# driver1.net
KiCad netlist of a schematic drawn in EAGLE
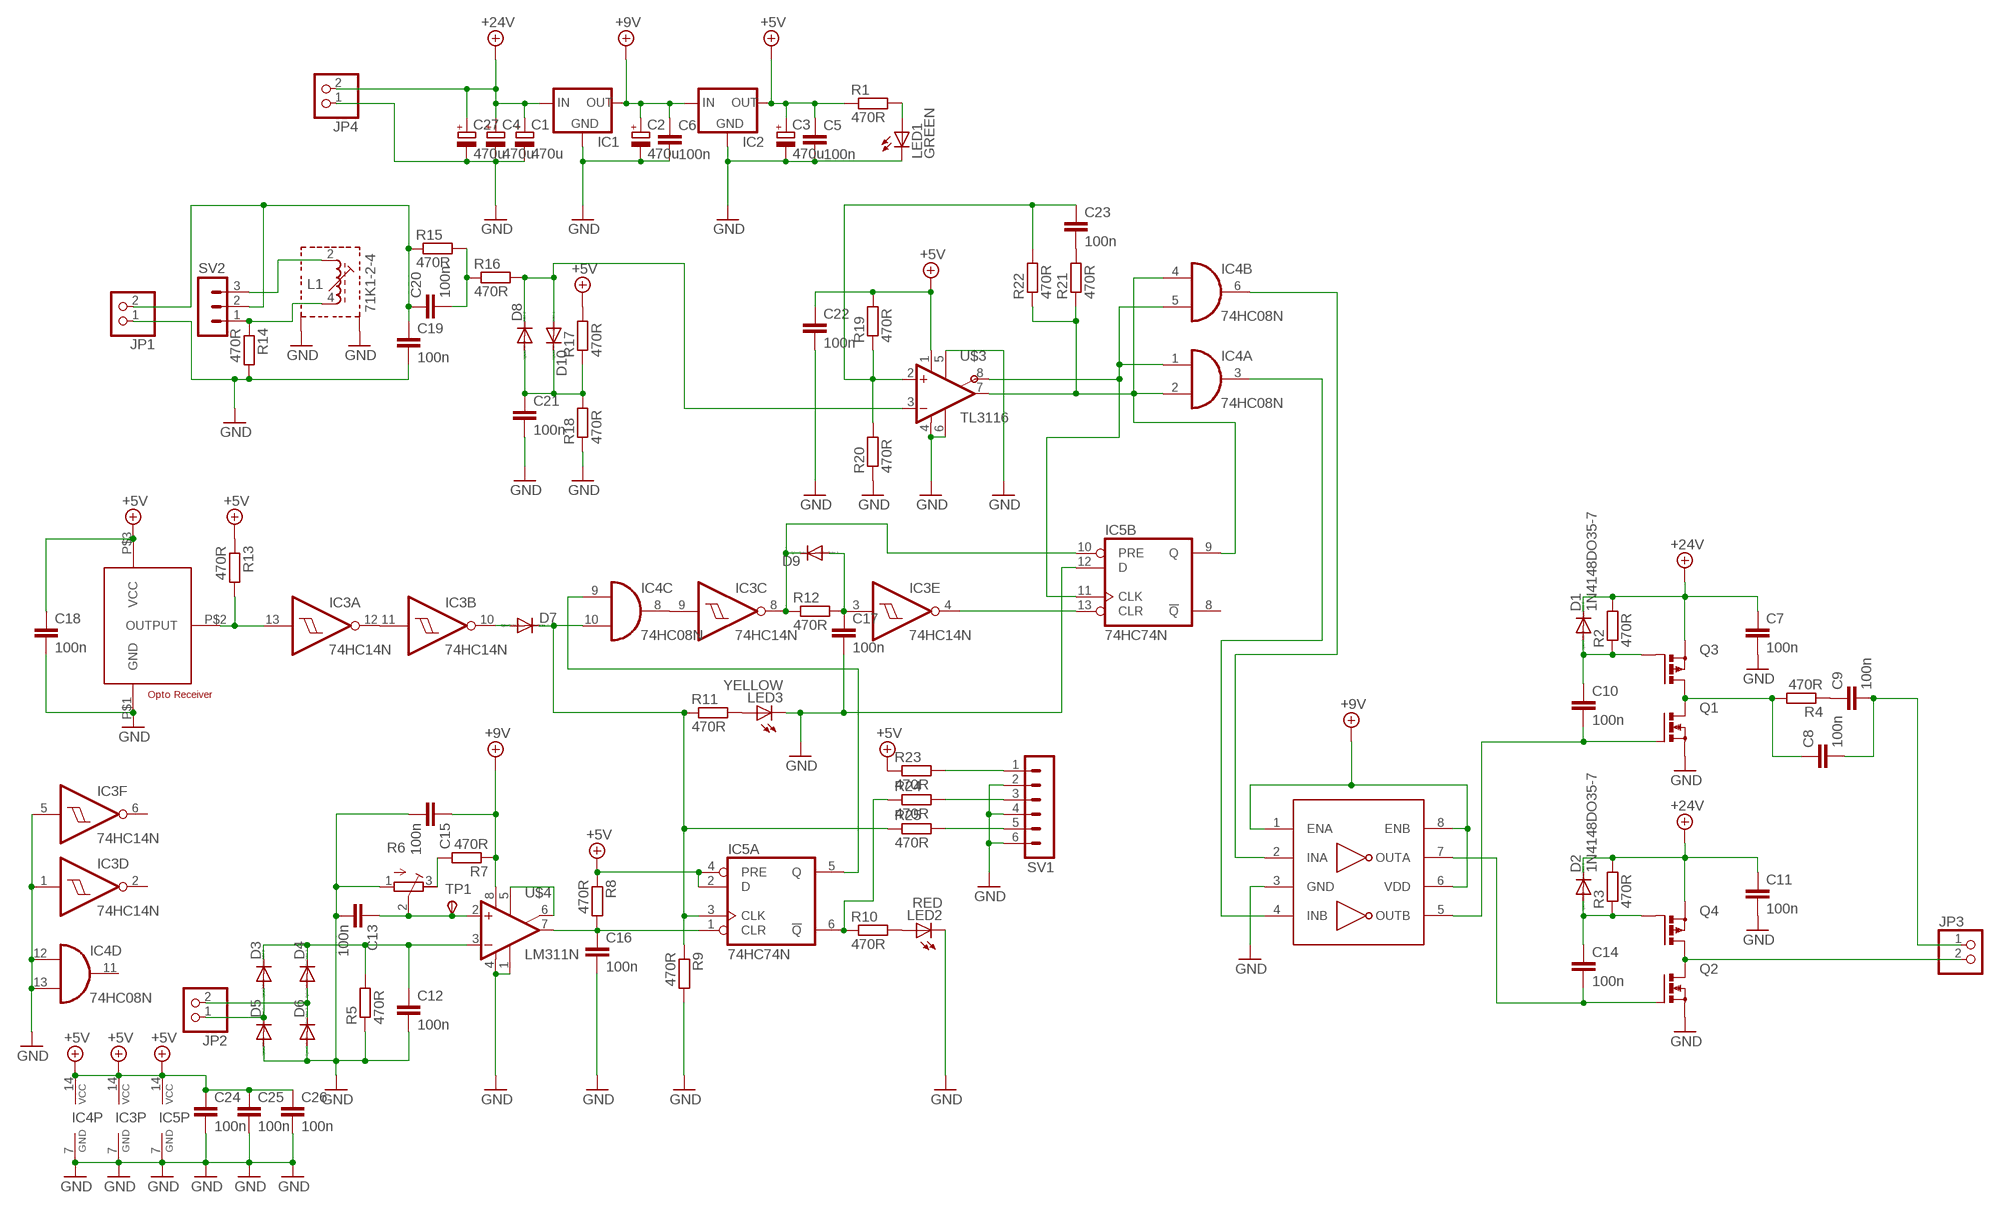
[diagram p0: schematic, sheet 1]

(export (version "E")
  (design (tool "Eeschema 10.0.6"))
  (components
    (comp (ref "C1")
      (value "470u")
      (footprint "eagle-import:E5-8,5")
      (libsource (lib "eagle-import") (part "CPOL-EUE5-8.5"))
    )
    (comp (ref "C2")
      (value "470u")
      (footprint "eagle-import:E5-8,5")
      (libsource (lib "eagle-import") (part "CPOL-EUE5-8.5"))
    )
    (comp (ref "C3")
      (value "470u")
      (footprint "eagle-import:E5-8,5")
      (libsource (lib "eagle-import") (part "CPOL-EUE5-8.5"))
    )
    (comp (ref "C4")
      (value "470u")
      (footprint "eagle-import:E5-8,5")
      (libsource (lib "eagle-import") (part "CPOL-EUE5-8.5"))
    )
    (comp (ref "C5")
      (value "100n")
      (footprint "eagle-import:C025-025X050")
      (libsource (lib "eagle-import") (part "C-EU025-025X050"))
    )
    (comp (ref "C6")
      (value "100n")
      (footprint "eagle-import:C025-025X050")
      (libsource (lib "eagle-import") (part "C-EU025-025X050"))
    )
    (comp (ref "C7")
      (value "100n")
      (footprint "eagle-import:C025-025X050")
      (libsource (lib "eagle-import") (part "C-EU025-025X050"))
    )
    (comp (ref "C8")
      (value "100n")
      (footprint "eagle-import:C025-025X050")
      (libsource (lib "eagle-import") (part "C-EU025-025X050"))
    )
    (comp (ref "C9")
      (value "100n")
      (footprint "eagle-import:C025-025X050")
      (libsource (lib "eagle-import") (part "C-EU025-025X050"))
    )
    (comp (ref "C10")
      (value "100n")
      (footprint "eagle-import:C025-025X050")
      (libsource (lib "eagle-import") (part "C-EU025-025X050"))
    )
    (comp (ref "C11")
      (value "100n")
      (footprint "eagle-import:C025-025X050")
      (libsource (lib "eagle-import") (part "C-EU025-025X050"))
    )
    (comp (ref "C12")
      (value "100n")
      (footprint "eagle-import:C025-025X050")
      (libsource (lib "eagle-import") (part "C-EU025-025X050"))
    )
    (comp (ref "C13")
      (value "100n")
      (footprint "eagle-import:C025-025X050")
      (libsource (lib "eagle-import") (part "C-EU025-025X050"))
    )
    (comp (ref "C14")
      (value "100n")
      (footprint "eagle-import:C025-025X050")
      (libsource (lib "eagle-import") (part "C-EU025-025X050"))
    )
    (comp (ref "C15")
      (value "100n")
      (footprint "eagle-import:C025-025X050")
      (libsource (lib "eagle-import") (part "C-EU025-025X050"))
    )
    (comp (ref "C16")
      (value "100n")
      (footprint "eagle-import:C025-025X050")
      (libsource (lib "eagle-import") (part "C-EU025-025X050"))
    )
    (comp (ref "C17")
      (value "100n")
      (footprint "eagle-import:C025-025X050")
      (libsource (lib "eagle-import") (part "C-EU025-025X050"))
    )
    (comp (ref "C18")
      (value "100n")
      (footprint "eagle-import:C025-025X050")
      (libsource (lib "eagle-import") (part "C-EU025-025X050"))
    )
    (comp (ref "C19")
      (value "100n")
      (footprint "eagle-import:C025-025X050")
      (libsource (lib "eagle-import") (part "C-EU025-025X050"))
    )
    (comp (ref "C20")
      (value "100n")
      (footprint "eagle-import:C025-025X050")
      (libsource (lib "eagle-import") (part "C-EU025-025X050"))
    )
    (comp (ref "C21")
      (value "100n")
      (footprint "eagle-import:C025-025X050")
      (libsource (lib "eagle-import") (part "C-EU025-025X050"))
    )
    (comp (ref "C22")
      (value "100n")
      (footprint "eagle-import:C025-025X050")
      (libsource (lib "eagle-import") (part "C-EU025-025X050"))
    )
    (comp (ref "C23")
      (value "100n")
      (footprint "eagle-import:C025-025X050")
      (libsource (lib "eagle-import") (part "C-EU025-025X050"))
    )
    (comp (ref "C24")
      (value "100n")
      (footprint "eagle-import:C025-025X050")
      (libsource (lib "eagle-import") (part "C-EU025-025X050"))
    )
    (comp (ref "C25")
      (value "100n")
      (footprint "eagle-import:C025-025X050")
      (libsource (lib "eagle-import") (part "C-EU025-025X050"))
    )
    (comp (ref "C26")
      (value "100n")
      (footprint "eagle-import:C025-025X050")
      (libsource (lib "eagle-import") (part "C-EU025-025X050"))
    )
    (comp (ref "C27")
      (value "470u")
      (footprint "eagle-import:E5-8,5")
      (libsource (lib "eagle-import") (part "CPOL-EUE5-8.5"))
    )
    (comp (ref "D1")
      (value "1N4148DO35-7")
      (footprint "eagle-import:DO35-7")
      (libsource (lib "eagle-import") (part "1N4148DO35-7"))
    )
    (comp (ref "D2")
      (value "1N4148DO35-7")
      (footprint "eagle-import:DO35-7")
      (libsource (lib "eagle-import") (part "1N4148DO35-7"))
    )
    (comp (ref "D3")
      (value "DIODE-D-7.5")
      (footprint "eagle-import:D-7.5")
      (libsource (lib "eagle-import") (part "DIODE-D-7.5"))
    )
    (comp (ref "D4")
      (value "DIODE-D-7.5")
      (footprint "eagle-import:D-7.5")
      (libsource (lib "eagle-import") (part "DIODE-D-7.5"))
    )
    (comp (ref "D5")
      (value "DIODE-D-7.5")
      (footprint "eagle-import:D-7.5")
      (libsource (lib "eagle-import") (part "DIODE-D-7.5"))
    )
    (comp (ref "D6")
      (value "DIODE-D-7.5")
      (footprint "eagle-import:D-7.5")
      (libsource (lib "eagle-import") (part "DIODE-D-7.5"))
    )
    (comp (ref "D7")
      (value "DIODE-D-7.5")
      (footprint "eagle-import:D-7.5")
      (libsource (lib "eagle-import") (part "DIODE-D-7.5"))
    )
    (comp (ref "D8")
      (value "DIODE-D-7.5")
      (footprint "eagle-import:D-7.5")
      (libsource (lib "eagle-import") (part "DIODE-D-7.5"))
    )
    (comp (ref "D9")
      (value "DIODE-D-7.5")
      (footprint "eagle-import:D-7.5")
      (libsource (lib "eagle-import") (part "DIODE-D-7.5"))
    )
    (comp (ref "D10")
      (value "DIODE-D-7.5")
      (footprint "eagle-import:D-7.5")
      (libsource (lib "eagle-import") (part "DIODE-D-7.5"))
    )
    (comp (ref "IC1")
      (value "78XXS")
      (footprint "eagle-import:78XXS")
      (libsource (lib "eagle-import") (part "78XXS"))
    )
    (comp (ref "IC2")
      (value "78XXS")
      (footprint "eagle-import:78XXS")
      (libsource (lib "eagle-import") (part "78XXS"))
    )
    (comp (ref "IC3")
      (value "74HC14N")
      (footprint "eagle-import:DIL14")
      (libsource (lib "eagle-import") (part "7414NHC"))
    )
    (comp (ref "IC4")
      (value "74HC08N")
      (footprint "eagle-import:DIL14")
      (libsource (lib "eagle-import") (part "7408NHC"))
    )
    (comp (ref "IC5")
      (value "74HC74N")
      (footprint "eagle-import:DIL14")
      (libsource (lib "eagle-import") (part "7474NHC"))
    )
    (comp (ref "JP1")
      (value "PINHD-1X2")
      (footprint "eagle-import:1X02")
      (libsource (lib "eagle-import") (part "PINHD-1X2"))
    )
    (comp (ref "JP2")
      (value "PINHD-1X2")
      (footprint "eagle-import:1X02")
      (libsource (lib "eagle-import") (part "PINHD-1X2"))
    )
    (comp (ref "JP3")
      (value "PINHD-1X2")
      (footprint "eagle-import:1X02")
      (libsource (lib "eagle-import") (part "PINHD-1X2"))
    )
    (comp (ref "JP4")
      (value "PINHD-1X2")
      (footprint "eagle-import:1X02")
      (libsource (lib "eagle-import") (part "PINHD-1X2"))
    )
    (comp (ref "L1")
      (value "71K1-2-4")
      (footprint "eagle-import:71K")
      (libsource (lib "eagle-import") (part "71K1-2-4"))
    )
    (comp (ref "LED1")
      (value "GREEN")
      (footprint "eagle-import:LED3MM")
      (libsource (lib "eagle-import") (part "LED3MM"))
    )
    (comp (ref "LED2")
      (value "RED")
      (footprint "eagle-import:LED3MM")
      (libsource (lib "eagle-import") (part "LED3MM"))
    )
    (comp (ref "LED3")
      (value "YELLOW")
      (footprint "eagle-import:LED3MM")
      (libsource (lib "eagle-import") (part "LED3MM"))
    )
    (comp (ref "Q1")
      (value "PMOSFET_NTO220BV")
      (footprint "eagle-import:TO220BV")
      (libsource (lib "eagle-import") (part "PMOSFET_NTO220BV"))
    )
    (comp (ref "Q2")
      (value "PMOSFET_NTO220BV")
      (footprint "eagle-import:TO220BV")
      (libsource (lib "eagle-import") (part "PMOSFET_NTO220BV"))
    )
    (comp (ref "Q3")
      (value "PMOSFET_PTO220BV")
      (footprint "eagle-import:TO220BV")
      (libsource (lib "eagle-import") (part "PMOSFET_PTO220BV"))
    )
    (comp (ref "Q4")
      (value "PMOSFET_PTO220BV")
      (footprint "eagle-import:TO220BV")
      (libsource (lib "eagle-import") (part "PMOSFET_PTO220BV"))
    )
    (comp (ref "R1")
      (value "470R")
      (footprint "eagle-import:0207_7")
      (libsource (lib "eagle-import") (part "R-EU_0207/7"))
    )
    (comp (ref "R2")
      (value "470R")
      (footprint "eagle-import:0207_7")
      (libsource (lib "eagle-import") (part "R-EU_0207/7"))
    )
    (comp (ref "R3")
      (value "470R")
      (footprint "eagle-import:0207_7")
      (libsource (lib "eagle-import") (part "R-EU_0207/7"))
    )
    (comp (ref "R4")
      (value "470R")
      (footprint "eagle-import:0207_7")
      (libsource (lib "eagle-import") (part "R-EU_0207/7"))
    )
    (comp (ref "R5")
      (value "470R")
      (footprint "eagle-import:0309_12")
      (libsource (lib "eagle-import") (part "R-EU_0309/12"))
    )
    (comp (ref "R6")
      (value "R-TRIMM64W")
      (footprint "eagle-import:RTRIM64W")
      (libsource (lib "eagle-import") (part "R-TRIMM64W"))
    )
    (comp (ref "R7")
      (value "470R")
      (footprint "eagle-import:0207_7")
      (libsource (lib "eagle-import") (part "R-EU_0207/7"))
    )
    (comp (ref "R8")
      (value "470R")
      (footprint "eagle-import:0207_7")
      (libsource (lib "eagle-import") (part "R-EU_0207/7"))
    )
    (comp (ref "R9")
      (value "470R")
      (footprint "eagle-import:0207_7")
      (libsource (lib "eagle-import") (part "R-EU_0207/7"))
    )
    (comp (ref "R10")
      (value "470R")
      (footprint "eagle-import:0207_7")
      (libsource (lib "eagle-import") (part "R-EU_0207/7"))
    )
    (comp (ref "R11")
      (value "470R")
      (footprint "eagle-import:0207_7")
      (libsource (lib "eagle-import") (part "R-EU_0207/7"))
    )
    (comp (ref "R12")
      (value "470R")
      (footprint "eagle-import:0207_7")
      (libsource (lib "eagle-import") (part "R-EU_0207/7"))
    )
    (comp (ref "R13")
      (value "470R")
      (footprint "eagle-import:0207_7")
      (libsource (lib "eagle-import") (part "R-EU_0207/7"))
    )
    (comp (ref "R14")
      (value "470R")
      (footprint "eagle-import:0207_7")
      (libsource (lib "eagle-import") (part "R-EU_0207/7"))
    )
    (comp (ref "R15")
      (value "470R")
      (footprint "eagle-import:0207_7")
      (libsource (lib "eagle-import") (part "R-EU_0207/7"))
    )
    (comp (ref "R16")
      (value "470R")
      (footprint "eagle-import:0207_7")
      (libsource (lib "eagle-import") (part "R-EU_0207/7"))
    )
    (comp (ref "R17")
      (value "470R")
      (footprint "eagle-import:0207_7")
      (libsource (lib "eagle-import") (part "R-EU_0207/7"))
    )
    (comp (ref "R18")
      (value "470R")
      (footprint "eagle-import:0207_7")
      (libsource (lib "eagle-import") (part "R-EU_0207/7"))
    )
    (comp (ref "R19")
      (value "470R")
      (footprint "eagle-import:0207_7")
      (libsource (lib "eagle-import") (part "R-EU_0207/7"))
    )
    (comp (ref "R20")
      (value "470R")
      (footprint "eagle-import:0207_7")
      (libsource (lib "eagle-import") (part "R-EU_0207/7"))
    )
    (comp (ref "R21")
      (value "470R")
      (footprint "eagle-import:0207_7")
      (libsource (lib "eagle-import") (part "R-EU_0207/7"))
    )
    (comp (ref "R22")
      (value "470R")
      (footprint "eagle-import:0207_7")
      (libsource (lib "eagle-import") (part "R-EU_0207/7"))
    )
    (comp (ref "R23")
      (value "470R")
      (footprint "eagle-import:0207_7")
      (libsource (lib "eagle-import") (part "R-EU_0207/7"))
    )
    (comp (ref "R24")
      (value "470R")
      (footprint "eagle-import:0207_7")
      (libsource (lib "eagle-import") (part "R-EU_0207/7"))
    )
    (comp (ref "R25")
      (value "470R")
      (footprint "eagle-import:0207_7")
      (libsource (lib "eagle-import") (part "R-EU_0207/7"))
    )
    (comp (ref "SV1")
      (value "MA06-1")
      (footprint "eagle-import:MA06-1")
      (libsource (lib "eagle-import") (part "MA06-1"))
    )
    (comp (ref "SV2")
      (value "MA03-1")
      (footprint "eagle-import:MA03-1")
      (libsource (lib "eagle-import") (part "MA03-1"))
    )
    (comp (ref "TP1")
      (value "TPSTP20R")
      (footprint "eagle-import:TP20R")
      (libsource (lib "eagle-import") (part "TPSTP20R"))
    )
    (comp (ref "U$1")
      (value "UCC27423")
      (footprint "eagle-import:DIL8")
      (libsource (lib "eagle-import") (part "UCC27423"))
    )
    (comp (ref "U$2")
      (value "IFD95")
      (footprint "eagle-import:OPTO-RECEIVER")
      (libsource (lib "eagle-import") (part "IFD95"))
    )
    (comp (ref "U$3")
      (value "TL3116")
      (footprint "eagle-import:DIL8")
      (libsource (lib "eagle-import") (part "TL3116"))
    )
    (comp (ref "U$4")
      (value "LM311N")
      (footprint "eagle-import:DIL8")
      (libsource (lib "eagle-import") (part "LM311N"))
    )
  )
  (nets
    (net (code "1") (name "+5V") (class "Default")
      (node (ref "C18") (pin "1") (pinfunction "1_1") (pintype "passive"))
      (node (ref "C22") (pin "1") (pinfunction "1_1") (pintype "passive"))
      (node (ref "C24") (pin "1") (pinfunction "1_1") (pintype "passive"))
      (node (ref "C25") (pin "1") (pinfunction "1_1") (pintype "passive"))
      (node (ref "C26") (pin "1") (pinfunction "1_1") (pintype "passive"))
      (node (ref "C3") (pin "+") (pinfunction "+_+") (pintype "passive"))
      (node (ref "C5") (pin "1") (pinfunction "1_1") (pintype "passive"))
      (node (ref "IC2") (pin "OUT") (pinfunction "OUT_OUT") (pintype "passive"))
      (node (ref "IC3") (pin "14") (pinfunction "VCC_14") (pintype "power_in"))
      (node (ref "IC4") (pin "14") (pinfunction "VCC_14") (pintype "power_in"))
      (node (ref "IC5") (pin "14") (pinfunction "VCC_14") (pintype "power_in"))
      (node (ref "IC5") (pin "2") (pinfunction "D_2") (pintype "input"))
      (node (ref "IC5") (pin "4") (pinfunction "PRE_4") (pintype "input"))
      (node (ref "R1") (pin "1") (pinfunction "1_1") (pintype "passive"))
      (node (ref "R13") (pin "1") (pinfunction "1_1") (pintype "passive"))
      (node (ref "R17") (pin "2") (pinfunction "2_2") (pintype "passive"))
      (node (ref "R19") (pin "2") (pinfunction "2_2") (pintype "passive"))
      (node (ref "R23") (pin "1") (pinfunction "1_1") (pintype "passive"))
      (node (ref "R8") (pin "1") (pinfunction "1_1") (pintype "passive"))
      (node (ref "U$2") (pin "P$3") (pinfunction "VCC_P$3") (pintype "bidirectional"))
      (node (ref "U$3") (pin "1") (pinfunction "V+_1") (pintype "power_in"))
    )
    (net (code "2") (name "+9V") (class "Default")
      (node (ref "C15") (pin "1") (pinfunction "1_1") (pintype "passive"))
      (node (ref "C2") (pin "+") (pinfunction "+_+") (pintype "passive"))
      (node (ref "C6") (pin "1") (pinfunction "1_1") (pintype "passive"))
      (node (ref "IC1") (pin "OUT") (pinfunction "OUT_OUT") (pintype "passive"))
      (node (ref "IC2") (pin "IN") (pinfunction "IN_IN") (pintype "input"))
      (node (ref "R7") (pin "1") (pinfunction "1_1") (pintype "passive"))
      (node (ref "U$1") (pin "1") (pinfunction "ENA_1") (pintype "bidirectional"))
      (node (ref "U$1") (pin "6") (pinfunction "VDD_6") (pintype "bidirectional"))
      (node (ref "U$1") (pin "8") (pinfunction "ENB_8") (pintype "bidirectional"))
      (node (ref "U$4") (pin "8") (pinfunction "V+_8") (pintype "power_in"))
    )
    (net (code "3") (name "+24V") (class "Default")
      (node (ref "C1") (pin "+") (pinfunction "+_+") (pintype "passive"))
      (node (ref "C11") (pin "1") (pinfunction "1_1") (pintype "passive"))
      (node (ref "C27") (pin "+") (pinfunction "+_+") (pintype "passive"))
      (node (ref "C4") (pin "+") (pinfunction "+_+") (pintype "passive"))
      (node (ref "C7") (pin "1") (pinfunction "1_1") (pintype "passive"))
      (node (ref "D1") (pin "C") (pinfunction "C_C") (pintype "passive"))
      (node (ref "D2") (pin "C") (pinfunction "C_C") (pintype "passive"))
      (node (ref "IC1") (pin "IN") (pinfunction "IN_IN") (pintype "input"))
      (node (ref "JP4") (pin "2") (pinfunction "2_2") (pintype "passive"))
      (node (ref "Q3") (pin "S") (pinfunction "S_S") (pintype "passive"))
      (node (ref "Q4") (pin "S") (pinfunction "S_S") (pintype "passive"))
      (node (ref "R2") (pin "2") (pinfunction "2_2") (pintype "passive"))
      (node (ref "R3") (pin "2") (pinfunction "2_2") (pintype "passive"))
    )
    (net (code "4") (name "GND") (class "Default")
      (node (ref "C1") (pin "-") (pinfunction "-_-") (pintype "passive"))
      (node (ref "C11") (pin "2") (pinfunction "2_2") (pintype "passive"))
      (node (ref "C12") (pin "2") (pinfunction "2_2") (pintype "passive"))
      (node (ref "C13") (pin "2") (pinfunction "2_2") (pintype "passive"))
      (node (ref "C15") (pin "2") (pinfunction "2_2") (pintype "passive"))
      (node (ref "C16") (pin "2") (pinfunction "2_2") (pintype "passive"))
      (node (ref "C17") (pin "2") (pinfunction "2_2") (pintype "passive"))
      (node (ref "C18") (pin "2") (pinfunction "2_2") (pintype "passive"))
      (node (ref "C19") (pin "2") (pinfunction "2_2") (pintype "passive"))
      (node (ref "C2") (pin "-") (pinfunction "-_-") (pintype "passive"))
      (node (ref "C21") (pin "2") (pinfunction "2_2") (pintype "passive"))
      (node (ref "C22") (pin "2") (pinfunction "2_2") (pintype "passive"))
      (node (ref "C24") (pin "2") (pinfunction "2_2") (pintype "passive"))
      (node (ref "C25") (pin "2") (pinfunction "2_2") (pintype "passive"))
      (node (ref "C26") (pin "2") (pinfunction "2_2") (pintype "passive"))
      (node (ref "C27") (pin "-") (pinfunction "-_-") (pintype "passive"))
      (node (ref "C3") (pin "-") (pinfunction "-_-") (pintype "passive"))
      (node (ref "C4") (pin "-") (pinfunction "-_-") (pintype "passive"))
      (node (ref "C5") (pin "2") (pinfunction "2_2") (pintype "passive"))
      (node (ref "C6") (pin "2") (pinfunction "2_2") (pintype "passive"))
      (node (ref "C7") (pin "2") (pinfunction "2_2") (pintype "passive"))
      (node (ref "D5") (pin "A") (pinfunction "A_A") (pintype "passive"))
      (node (ref "D6") (pin "A") (pinfunction "A_A") (pintype "passive"))
      (node (ref "IC1") (pin "GND") (pinfunction "GND_GND") (pintype "input"))
      (node (ref "IC2") (pin "GND") (pinfunction "GND_GND") (pintype "input"))
      (node (ref "IC3") (pin "1") (pinfunction "I_1") (pintype "input"))
      (node (ref "IC3") (pin "5") (pinfunction "I_5") (pintype "input"))
      (node (ref "IC3") (pin "7") (pinfunction "GND_7") (pintype "power_in"))
      (node (ref "IC4") (pin "12") (pinfunction "I0_12") (pintype "input"))
      (node (ref "IC4") (pin "13") (pinfunction "I1_13") (pintype "input"))
      (node (ref "IC4") (pin "7") (pinfunction "GND_7") (pintype "power_in"))
      (node (ref "IC5") (pin "12") (pinfunction "D_12") (pintype "input"))
      (node (ref "IC5") (pin "7") (pinfunction "GND_7") (pintype "power_in"))
      (node (ref "JP1") (pin "1") (pinfunction "1_1") (pintype "passive"))
      (node (ref "JP4") (pin "1") (pinfunction "1_1") (pintype "passive"))
      (node (ref "L1") (pin "S1") (pinfunction "S1_S1") (pintype "passive"))
      (node (ref "L1") (pin "S2") (pinfunction "S2_S2") (pintype "passive"))
      (node (ref "LED1") (pin "K") (pinfunction "C_K") (pintype "passive"))
      (node (ref "LED2") (pin "K") (pinfunction "C_K") (pintype "passive"))
      (node (ref "LED3") (pin "K") (pinfunction "C_K") (pintype "passive"))
      (node (ref "Q1") (pin "S") (pinfunction "S_S") (pintype "passive"))
      (node (ref "Q2") (pin "S") (pinfunction "S_S") (pintype "passive"))
      (node (ref "R14") (pin "2") (pinfunction "2_2") (pintype "passive"))
      (node (ref "R18") (pin "1") (pinfunction "1_1") (pintype "passive"))
      (node (ref "R20") (pin "1") (pinfunction "1_1") (pintype "passive"))
      (node (ref "R5") (pin "1") (pinfunction "1_1") (pintype "passive"))
      (node (ref "R6") (pin "1") (pinfunction "A_1") (pintype "passive"))
      (node (ref "R9") (pin "2") (pinfunction "2_2") (pintype "passive"))
      (node (ref "SV1") (pin "2") (pinfunction "2_2") (pintype "passive"))
      (node (ref "SV1") (pin "4") (pinfunction "4_4") (pintype "passive"))
      (node (ref "SV1") (pin "6") (pinfunction "6_6") (pintype "passive"))
      (node (ref "U$1") (pin "3") (pinfunction "GND_3") (pintype "bidirectional"))
      (node (ref "U$2") (pin "P$1") (pinfunction "GND_P$1") (pintype "bidirectional"))
      (node (ref "U$3") (pin "4") (pinfunction "V-_4") (pintype "power_in"))
      (node (ref "U$3") (pin "5") (pinfunction "LEN_5") (pintype "passive"))
      (node (ref "U$3") (pin "6") (pinfunction "GND_6") (pintype "passive"))
      (node (ref "U$4") (pin "1") (pinfunction "GND_1") (pintype "passive"))
      (node (ref "U$4") (pin "4") (pinfunction "V-_4") (pintype "power_in"))
    )
    (net (code "5") (name "Net-(C8-Pad1)") (class "Default")
      (node (ref "C8") (pin "1") (pinfunction "1_1") (pintype "passive"))
      (node (ref "Q1") (pin "D") (pinfunction "D_D") (pintype "passive"))
      (node (ref "Q3") (pin "D") (pinfunction "D_D") (pintype "passive"))
      (node (ref "R4") (pin "2") (pinfunction "2_2") (pintype "passive"))
    )
    (net (code "6") (name "Net-(C8-Pad2)") (class "Default")
      (node (ref "C8") (pin "2") (pinfunction "2_2") (pintype "passive"))
      (node (ref "C9") (pin "2") (pinfunction "2_2") (pintype "passive"))
      (node (ref "JP3") (pin "1") (pinfunction "1_1") (pintype "passive"))
    )
    (net (code "7") (name "Net-(C9-Pad1)") (class "Default")
      (node (ref "C9") (pin "1") (pinfunction "1_1") (pintype "passive"))
      (node (ref "R4") (pin "1") (pinfunction "1_1") (pintype "passive"))
    )
    (net (code "8") (name "Net-(C10-Pad1)") (class "Default")
      (node (ref "C10") (pin "1") (pinfunction "1_1") (pintype "passive"))
      (node (ref "D1") (pin "A") (pinfunction "A_A") (pintype "passive"))
      (node (ref "Q3") (pin "G") (pinfunction "G_G") (pintype "passive"))
      (node (ref "R2") (pin "1") (pinfunction "1_1") (pintype "passive"))
    )
    (net (code "9") (name "Net-(C14-Pad1)") (class "Default")
      (node (ref "C14") (pin "1") (pinfunction "1_1") (pintype "passive"))
      (node (ref "D2") (pin "A") (pinfunction "A_A") (pintype "passive"))
      (node (ref "Q4") (pin "G") (pinfunction "G_G") (pintype "passive"))
      (node (ref "R3") (pin "1") (pinfunction "1_1") (pintype "passive"))
    )
    (net (code "10") (name "Net-(C19-Pad1)") (class "Default")
      (node (ref "C19") (pin "1") (pinfunction "1_1") (pintype "passive"))
      (node (ref "C20") (pin "1") (pinfunction "1_1") (pintype "passive"))
      (node (ref "JP1") (pin "2") (pinfunction "2_2") (pintype "passive"))
      (node (ref "R15") (pin "1") (pinfunction "1_1") (pintype "passive"))
      (node (ref "SV2") (pin "2") (pinfunction "2_2") (pintype "passive"))
    )
    (net (code "11") (name "Net-(C20-Pad2)") (class "Default")
      (node (ref "C20") (pin "2") (pinfunction "2_2") (pintype "passive"))
      (node (ref "R15") (pin "2") (pinfunction "2_2") (pintype "passive"))
      (node (ref "R16") (pin "1") (pinfunction "1_1") (pintype "passive"))
    )
    (net (code "12") (name "Net-(C21-Pad1)") (class "Default")
      (node (ref "C21") (pin "1") (pinfunction "1_1") (pintype "passive"))
      (node (ref "D10") (pin "C") (pinfunction "C_C") (pintype "passive"))
      (node (ref "D8") (pin "A") (pinfunction "A_A") (pintype "passive"))
      (node (ref "R17") (pin "1") (pinfunction "1_1") (pintype "passive"))
      (node (ref "R18") (pin "2") (pinfunction "2_2") (pintype "passive"))
    )
    (net (code "13") (name "Net-(C23-Pad2)") (class "Default")
      (node (ref "C23") (pin "2") (pinfunction "2_2") (pintype "passive"))
      (node (ref "R21") (pin "2") (pinfunction "2_2") (pintype "passive"))
    )
    (net (code "14") (name "Net-(D3-PadA)") (class "Default")
      (node (ref "D3") (pin "A") (pinfunction "A_A") (pintype "passive"))
      (node (ref "D5") (pin "C") (pinfunction "C_C") (pintype "passive"))
      (node (ref "JP2") (pin "1") (pinfunction "1_1") (pintype "passive"))
    )
    (net (code "15") (name "Net-(D4-PadA)") (class "Default")
      (node (ref "D4") (pin "A") (pinfunction "A_A") (pintype "passive"))
      (node (ref "D6") (pin "C") (pinfunction "C_C") (pintype "passive"))
      (node (ref "JP2") (pin "2") (pinfunction "2_2") (pintype "passive"))
    )
    (net (code "16") (name "Net-(IC3A-I)") (class "Default")
      (node (ref "IC3") (pin "13") (pinfunction "I_13") (pintype "input"))
      (node (ref "R13") (pin "2") (pinfunction "2_2") (pintype "passive"))
      (node (ref "U$2") (pin "P$2") (pinfunction "OUTPUT_P$2") (pintype "bidirectional"))
    )
    (net (code "17") (name "Net-(IC3A-O)") (class "Default")
      (node (ref "IC3") (pin "11") (pinfunction "I_11") (pintype "input"))
      (node (ref "IC3") (pin "12") (pinfunction "O_12") (pintype "output"))
    )
    (net (code "18") (name "Net-(IC3B-O)") (class "Default")
      (node (ref "D7") (pin "A") (pinfunction "A_A") (pintype "passive"))
      (node (ref "IC3") (pin "10") (pinfunction "O_10") (pintype "output"))
    )
    (net (code "19") (name "Net-(IC3C-I)") (class "Default")
      (node (ref "IC3") (pin "9") (pinfunction "I_9") (pintype "input"))
      (node (ref "IC4") (pin "8") (pinfunction "O_8") (pintype "output"))
    )
    (net (code "20") (name "Net-(IC3C-O)") (class "Default")
      (node (ref "D9") (pin "C") (pinfunction "C_C") (pintype "passive"))
      (node (ref "IC3") (pin "8") (pinfunction "O_8") (pintype "output"))
      (node (ref "IC5") (pin "10") (pinfunction "PRE_10") (pintype "input"))
      (node (ref "R12") (pin "1") (pinfunction "1_1") (pintype "passive"))
    )
    (net (code "21") (name "Net-(IC3E-I)") (class "Default")
      (node (ref "C17") (pin "1") (pinfunction "1_1") (pintype "passive"))
      (node (ref "D9") (pin "A") (pinfunction "A_A") (pintype "passive"))
      (node (ref "IC3") (pin "3") (pinfunction "I_3") (pintype "input"))
      (node (ref "R12") (pin "2") (pinfunction "2_2") (pintype "passive"))
    )
    (net (code "22") (name "Net-(IC3E-O)") (class "Default")
      (node (ref "IC3") (pin "4") (pinfunction "O_4") (pintype "output"))
      (node (ref "IC5") (pin "13") (pinfunction "CLR_13") (pintype "input"))
    )
    (net (code "23") (name "Net-(IC4A-I0)") (class "Default")
      (node (ref "IC4") (pin "1") (pinfunction "I0_1") (pintype "input"))
      (node (ref "IC4") (pin "5") (pinfunction "I1_5") (pintype "input"))
      (node (ref "IC5") (pin "11") (pinfunction "CLK_11") (pintype "input"))
      (node (ref "U$3") (pin "8") (pinfunction "~{OUT}_8") (pintype "passive"))
    )
    (net (code "24") (name "Net-(IC4A-I1)") (class "Default")
      (node (ref "IC4") (pin "2") (pinfunction "I1_2") (pintype "input"))
      (node (ref "IC4") (pin "4") (pinfunction "I0_4") (pintype "input"))
      (node (ref "IC5") (pin "9") (pinfunction "Q_9") (pintype "output"))
      (node (ref "R21") (pin "1") (pinfunction "1_1") (pintype "passive"))
      (node (ref "R22") (pin "1") (pinfunction "1_1") (pintype "passive"))
      (node (ref "U$3") (pin "7") (pinfunction "OUT_7") (pintype "output"))
    )
    (net (code "25") (name "Net-(IC4A-O)") (class "Default")
      (node (ref "IC4") (pin "3") (pinfunction "O_3") (pintype "output"))
      (node (ref "U$1") (pin "4") (pinfunction "INB_4") (pintype "bidirectional"))
    )
    (net (code "26") (name "Net-(IC4B-O)") (class "Default")
      (node (ref "IC4") (pin "6") (pinfunction "O_6") (pintype "output"))
      (node (ref "U$1") (pin "2") (pinfunction "INA_2") (pintype "bidirectional"))
    )
    (net (code "27") (name "Net-(IC4C-I0)") (class "Default")
      (node (ref "IC4") (pin "9") (pinfunction "I0_9") (pintype "input"))
      (node (ref "IC5") (pin "5") (pinfunction "Q_5") (pintype "output"))
    )
    (net (code "28") (name "Net-(IC4C-I1)") (class "Default")
      (node (ref "D7") (pin "C") (pinfunction "C_C") (pintype "passive"))
      (node (ref "IC4") (pin "10") (pinfunction "I1_10") (pintype "input"))
      (node (ref "IC5") (pin "3") (pinfunction "CLK_3") (pintype "input"))
      (node (ref "R11") (pin "1") (pinfunction "1_1") (pintype "passive"))
      (node (ref "R25") (pin "1") (pinfunction "1_1") (pintype "passive"))
      (node (ref "R9") (pin "1") (pinfunction "1_1") (pintype "passive"))
    )
    (net (code "29") (name "Net-(IC5A-CLR)") (class "Default")
      (node (ref "C16") (pin "1") (pinfunction "1_1") (pintype "passive"))
      (node (ref "IC5") (pin "1") (pinfunction "CLR_1") (pintype "input"))
      (node (ref "R8") (pin "2") (pinfunction "2_2") (pintype "passive"))
      (node (ref "U$4") (pin "7") (pinfunction "OUT_7") (pintype "output"))
    )
    (net (code "30") (name "Net-(IC5A-~{Q})") (class "Default")
      (node (ref "IC5") (pin "6") (pinfunction "~{Q}_6") (pintype "output"))
      (node (ref "R10") (pin "1") (pinfunction "1_1") (pintype "passive"))
      (node (ref "R24") (pin "1") (pinfunction "1_1") (pintype "passive"))
    )
    (net (code "31") (name "Net-(JP3-Pad2)") (class "Default")
      (node (ref "JP3") (pin "2") (pinfunction "2_2") (pintype "passive"))
      (node (ref "Q2") (pin "D") (pinfunction "D_D") (pintype "passive"))
      (node (ref "Q4") (pin "D") (pinfunction "D_D") (pintype "passive"))
    )
    (net (code "32") (name "Net-(L1A-A)") (class "Default")
      (node (ref "L1") (pin "2") (pinfunction "A_2") (pintype "passive"))
      (node (ref "SV2") (pin "3") (pinfunction "3_3") (pintype "passive"))
    )
    (net (code "33") (name "Net-(L1A-E)") (class "Default")
      (node (ref "L1") (pin "4") (pinfunction "E_4") (pintype "passive"))
      (node (ref "R14") (pin "1") (pinfunction "1_1") (pintype "passive"))
      (node (ref "SV2") (pin "1") (pinfunction "1_1") (pintype "passive"))
    )
    (net (code "34") (name "Net-(LED1-PadA)") (class "Default")
      (node (ref "LED1") (pin "A") (pinfunction "A_A") (pintype "passive"))
      (node (ref "R1") (pin "2") (pinfunction "2_2") (pintype "passive"))
    )
    (net (code "35") (name "Net-(LED2-PadA)") (class "Default")
      (node (ref "LED2") (pin "A") (pinfunction "A_A") (pintype "passive"))
      (node (ref "R10") (pin "2") (pinfunction "2_2") (pintype "passive"))
    )
    (net (code "36") (name "Net-(LED3-PadA)") (class "Default")
      (node (ref "LED3") (pin "A") (pinfunction "A_A") (pintype "passive"))
      (node (ref "R11") (pin "2") (pinfunction "2_2") (pintype "passive"))
    )
    (net (code "37") (name "Net-(R6-E)") (class "Default")
      (node (ref "R6") (pin "3") (pinfunction "E_3") (pintype "passive"))
      (node (ref "R7") (pin "2") (pinfunction "2_2") (pintype "passive"))
    )
    (net (code "38") (name "Net-(R6-S)") (class "Default")
      (node (ref "C13") (pin "1") (pinfunction "1_1") (pintype "passive"))
      (node (ref "R6") (pin "2") (pinfunction "S_2") (pintype "passive"))
      (node (ref "TP1") (pin "TP") (pinfunction "PP_TP") (pintype "input"))
      (node (ref "U$4") (pin "2") (pinfunction "+IN_2") (pintype "input"))
    )
    (net (code "39") (name "Net-(R23-Pad2)") (class "Default")
      (node (ref "R23") (pin "2") (pinfunction "2_2") (pintype "passive"))
      (node (ref "SV1") (pin "1") (pinfunction "1_1") (pintype "passive"))
    )
    (net (code "40") (name "Net-(R24-Pad2)") (class "Default")
      (node (ref "R24") (pin "2") (pinfunction "2_2") (pintype "passive"))
      (node (ref "SV1") (pin "3") (pinfunction "3_3") (pintype "passive"))
    )
    (net (code "41") (name "Net-(R25-Pad2)") (class "Default")
      (node (ref "R25") (pin "2") (pinfunction "2_2") (pintype "passive"))
      (node (ref "SV1") (pin "5") (pinfunction "5_5") (pintype "passive"))
    )
    (net (code "42") (name "Net-(U$1-OUTA)") (class "Default")
      (node (ref "C14") (pin "2") (pinfunction "2_2") (pintype "passive"))
      (node (ref "Q2") (pin "G") (pinfunction "G_G") (pintype "passive"))
      (node (ref "U$1") (pin "7") (pinfunction "OUTA_7") (pintype "bidirectional"))
    )
    (net (code "43") (name "Net-(U$1-OUTB)") (class "Default")
      (node (ref "C10") (pin "2") (pinfunction "2_2") (pintype "passive"))
      (node (ref "Q1") (pin "G") (pinfunction "G_G") (pintype "passive"))
      (node (ref "U$1") (pin "5") (pinfunction "OUTB_5") (pintype "bidirectional"))
    )
    (net (code "44") (name "Net-(U$3-+IN)") (class "Default")
      (node (ref "C23") (pin "1") (pinfunction "1_1") (pintype "passive"))
      (node (ref "R19") (pin "1") (pinfunction "1_1") (pintype "passive"))
      (node (ref "R20") (pin "2") (pinfunction "2_2") (pintype "passive"))
      (node (ref "R22") (pin "2") (pinfunction "2_2") (pintype "passive"))
      (node (ref "U$3") (pin "2") (pinfunction "+IN_2") (pintype "input"))
    )
    (net (code "45") (name "Net-(U$3--IN)") (class "Default")
      (node (ref "D10") (pin "A") (pinfunction "A_A") (pintype "passive"))
      (node (ref "D8") (pin "C") (pinfunction "C_C") (pintype "passive"))
      (node (ref "R16") (pin "2") (pinfunction "2_2") (pintype "passive"))
      (node (ref "U$3") (pin "3") (pinfunction "-IN_3") (pintype "input"))
    )
    (net (code "46") (name "Net-(U$4--IN)") (class "Default")
      (node (ref "C12") (pin "1") (pinfunction "1_1") (pintype "passive"))
      (node (ref "D3") (pin "C") (pinfunction "C_C") (pintype "passive"))
      (node (ref "D4") (pin "C") (pinfunction "C_C") (pintype "passive"))
      (node (ref "R5") (pin "2") (pinfunction "2_2") (pintype "passive"))
      (node (ref "U$4") (pin "3") (pinfunction "-IN_3") (pintype "input"))
    )
    (net (code "47") (name "Net-(U$4-ON)") (class "Default")
      (node (ref "U$4") (pin "5") (pinfunction "ON_5") (pintype "passive"))
      (node (ref "U$4") (pin "6") (pinfunction "ON/STR_6") (pintype "passive"))
    )
    (net (code "48") (name "unconnected-(IC3D-O-Pad2)") (class "Default")
      (node (ref "IC3") (pin "2") (pinfunction "O_2") (pintype "output"))
    )
    (net (code "49") (name "unconnected-(IC3F-O-Pad6)") (class "Default")
      (node (ref "IC3") (pin "6") (pinfunction "O_6") (pintype "output"))
    )
    (net (code "50") (name "unconnected-(IC4D-O-Pad11)") (class "Default")
      (node (ref "IC4") (pin "11") (pinfunction "O_11") (pintype "output"))
    )
    (net (code "51") (name "unconnected-(IC5B-~{Q}-Pad8)") (class "Default")
      (node (ref "IC5") (pin "8") (pinfunction "~{Q}_8") (pintype "output"))
    )
  )
)
